# display_board_ATMega4809.net
KiCad netlist of a schematic drawn in EAGLE
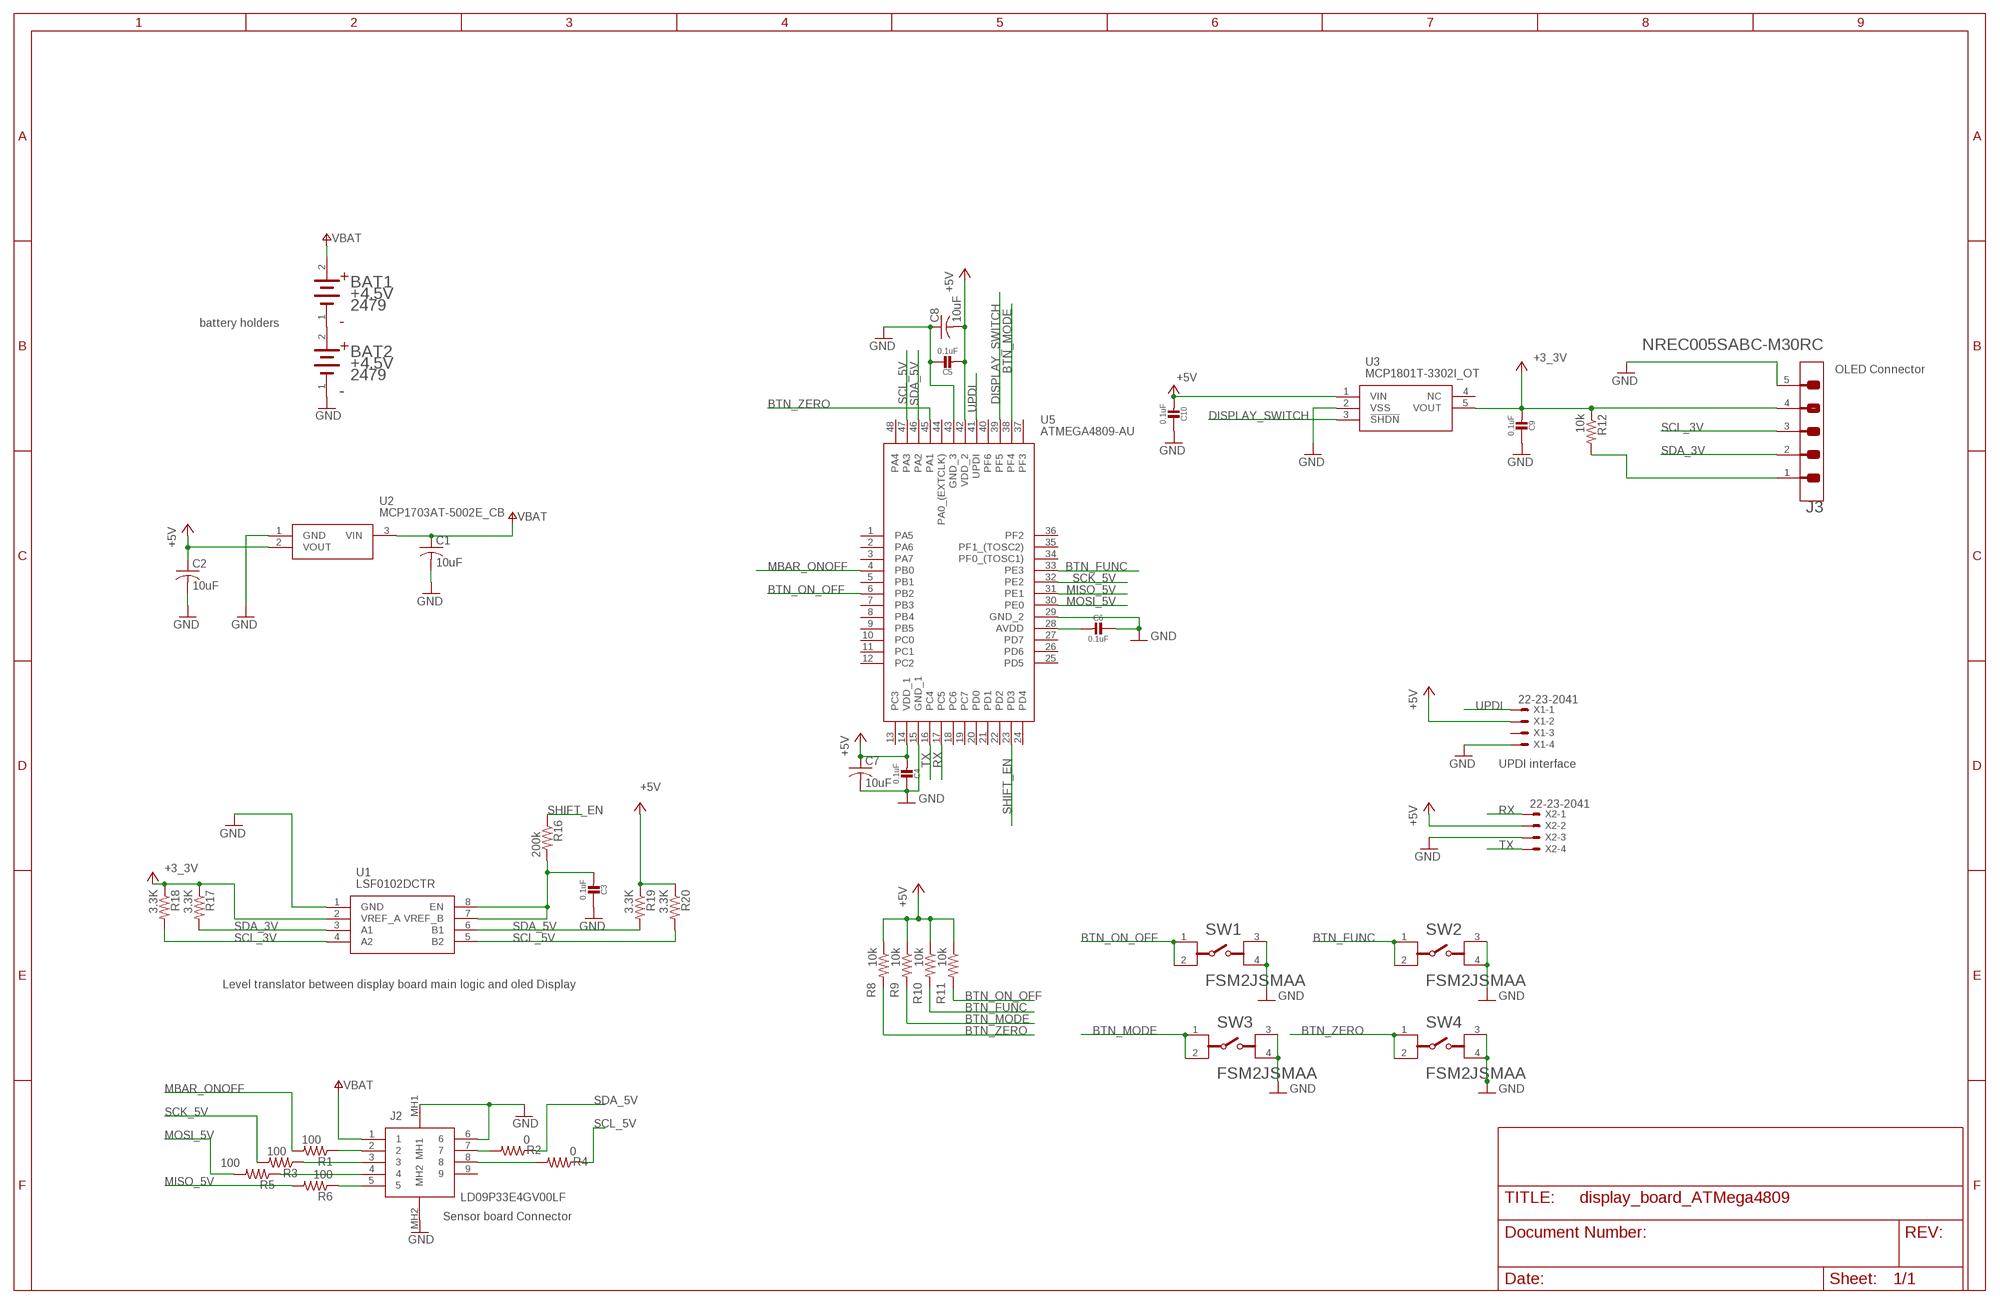
[diagram p0: schematic, sheet 1]

(export (version "E")
  (design (tool "Eeschema 10.0.6"))
  (components
    (comp (ref "BAT1")
      (value "KEYSTONE_2479KEYSTONE_2479_0_0")
      (footprint "eagle-import:KEYSTONE_2479_0")
      (fields
        (field (name "DIGIKEY_PART_NUMBER") "36-2479-ND")
        (field (name "MF") "Keystone")
        (field (name "MOUSER_PART_NUMBER") "534-2479")
      )
      (libsource (lib "eagle-import") (part "KEYSTONE_2479KEYSTONE_2479_0_0"))
    )
    (comp (ref "BAT2")
      (value "KEYSTONE_2479KEYSTONE_2479_0_0")
      (footprint "eagle-import:KEYSTONE_2479_0")
      (fields
        (field (name "DIGIKEY_PART_NUMBER") "36-2479-ND")
        (field (name "MF") "Keystone")
        (field (name "MOUSER_PART_NUMBER") "534-2479")
      )
      (libsource (lib "eagle-import") (part "KEYSTONE_2479KEYSTONE_2479_0_0"))
    )
    (comp (ref "C1")
      (value "10uF")
      (footprint "eagle-import:C0805")
      (libsource (lib "eagle-import") (part "C-USC0805"))
    )
    (comp (ref "C2")
      (value "10uF")
      (footprint "eagle-import:C0805")
      (libsource (lib "eagle-import") (part "C-USC0805"))
    )
    (comp (ref "C3")
      (value "0.1uF")
      (footprint "eagle-import:_0603MP")
      (libsource (lib "eagle-import") (part "CAP_CERAMIC_0603MP"))
    )
    (comp (ref "C4")
      (value "0.1uF")
      (footprint "eagle-import:_0603MP")
      (libsource (lib "eagle-import") (part "CAP_CERAMIC_0603MP"))
    )
    (comp (ref "C5")
      (value "0.1uF")
      (footprint "eagle-import:_0603MP")
      (libsource (lib "eagle-import") (part "CAP_CERAMIC_0603MP"))
    )
    (comp (ref "C6")
      (value "0.1uF")
      (footprint "eagle-import:_0603MP")
      (libsource (lib "eagle-import") (part "CAP_CERAMIC_0603MP"))
    )
    (comp (ref "C7")
      (value "10uF")
      (footprint "eagle-import:C0805")
      (libsource (lib "eagle-import") (part "C-USC0805"))
    )
    (comp (ref "C8")
      (value "10uF")
      (footprint "eagle-import:C0805")
      (libsource (lib "eagle-import") (part "C-USC0805"))
    )
    (comp (ref "C9")
      (value "0.1uF")
      (footprint "eagle-import:_0603MP")
      (libsource (lib "eagle-import") (part "CAP_CERAMIC_0603MP"))
    )
    (comp (ref "C10")
      (value "0.1uF")
      (footprint "eagle-import:_0603MP")
      (libsource (lib "eagle-import") (part "CAP_CERAMIC_0603MP"))
    )
    (comp (ref "J2")
      (value "LD09P33E4GV00LF")
      (footprint "eagle-import:LD09P33E4GV00LF")
      (fields (field (name "MOUSER_PART_NUMBER") "649-LD09P33E4GV00LF"))
      (libsource (lib "eagle-import") (part "LD09P33E4GV00LF"))
    )
    (comp (ref "J3")
      (value "SULLINS_NREC005SABC-M30RCSULLINS_NREC005SABC-M30RC_0_0")
      (footprint "eagle-import:SULLINS_NREC005SABC-M30RC_0")
      (fields
        (field (name "DIGIKEY_PART_NUMBER") "CONN HEADER .100\" SNGL SMD 5POS")
        (field (name "MF") "Sullins")
        (field (name "MPN") "NREC005SABC-M30RC")
      )
      (libsource (lib "eagle-import") (part "SULLINS_NREC005SABC-M30RCSULLINS_NREC005SABC-M30RC_0_0"))
    )
    (comp (ref "R1")
      (value "100")
      (footprint "eagle-import:R0603")
      (libsource (lib "eagle-import") (part "R-US_R0603"))
    )
    (comp (ref "R2")
      (value "0")
      (footprint "eagle-import:R0603")
      (libsource (lib "eagle-import") (part "R-US_R0603"))
    )
    (comp (ref "R3")
      (value "100")
      (footprint "eagle-import:R0603")
      (libsource (lib "eagle-import") (part "R-US_R0603"))
    )
    (comp (ref "R4")
      (value "0")
      (footprint "eagle-import:R0603")
      (libsource (lib "eagle-import") (part "R-US_R0603"))
    )
    (comp (ref "R5")
      (value "100")
      (footprint "eagle-import:R0603")
      (libsource (lib "eagle-import") (part "R-US_R0603"))
    )
    (comp (ref "R6")
      (value "100")
      (footprint "eagle-import:R0603")
      (libsource (lib "eagle-import") (part "R-US_R0603"))
    )
    (comp (ref "R8")
      (value "10k")
      (footprint "eagle-import:R0603")
      (libsource (lib "eagle-import") (part "R-US_R0603"))
    )
    (comp (ref "R9")
      (value "10k")
      (footprint "eagle-import:R0603")
      (libsource (lib "eagle-import") (part "R-US_R0603"))
    )
    (comp (ref "R10")
      (value "10k")
      (footprint "eagle-import:R0603")
      (libsource (lib "eagle-import") (part "R-US_R0603"))
    )
    (comp (ref "R11")
      (value "10k")
      (footprint "eagle-import:R0603")
      (libsource (lib "eagle-import") (part "R-US_R0603"))
    )
    (comp (ref "R12")
      (value "10k")
      (footprint "eagle-import:R0603")
      (libsource (lib "eagle-import") (part "R-US_R0603"))
    )
    (comp (ref "R16")
      (value "200k")
      (footprint "eagle-import:R0603")
      (libsource (lib "eagle-import") (part "R-US_R0603"))
    )
    (comp (ref "R17")
      (value "3.3K")
      (footprint "eagle-import:R0603")
      (libsource (lib "eagle-import") (part "R-US_R0603"))
    )
    (comp (ref "R18")
      (value "3.3K")
      (footprint "eagle-import:R0603")
      (libsource (lib "eagle-import") (part "R-US_R0603"))
    )
    (comp (ref "R19")
      (value "3.3K")
      (footprint "eagle-import:R0603")
      (libsource (lib "eagle-import") (part "R-US_R0603"))
    )
    (comp (ref "R20")
      (value "3.3K")
      (footprint "eagle-import:R0603")
      (libsource (lib "eagle-import") (part "R-US_R0603"))
    )
    (comp (ref "SW1")
      (value "TE_CONNECTIVITY_FSM2JSMAATE_CONNECTIVITY_FSM2JSMAA_0_0")
      (footprint "eagle-import:TE_CONNECTIVITY_FSM2JSMAA_0")
      (fields
        (field (name "DIGIKEY_PART_NUMBER") "450-3355-ND")
        (field (name "MF") "TE Connectivity")
        (field (name "MOUSER_PART_NUMBER") "506-2-1437565-8")
      )
      (libsource (lib "eagle-import") (part "TE_CONNECTIVITY_FSM2JSMAATE_CONNECTIVITY_FSM2JSMAA_0_0"))
    )
    (comp (ref "SW2")
      (value "TE_CONNECTIVITY_FSM2JSMAATE_CONNECTIVITY_FSM2JSMAA_0_0")
      (footprint "eagle-import:TE_CONNECTIVITY_FSM2JSMAA_0")
      (fields
        (field (name "DIGIKEY_PART_NUMBER") "450-3355-ND")
        (field (name "MF") "TE Connectivity")
        (field (name "MOUSER_PART_NUMBER") "506-2-1437565-8")
      )
      (libsource (lib "eagle-import") (part "TE_CONNECTIVITY_FSM2JSMAATE_CONNECTIVITY_FSM2JSMAA_0_0"))
    )
    (comp (ref "SW3")
      (value "TE_CONNECTIVITY_FSM2JSMAATE_CONNECTIVITY_FSM2JSMAA_0_0")
      (footprint "eagle-import:TE_CONNECTIVITY_FSM2JSMAA_0")
      (fields
        (field (name "DIGIKEY_PART_NUMBER") "450-3355-ND")
        (field (name "MF") "TE Connectivity")
        (field (name "MOUSER_PART_NUMBER") "506-2-1437565-8")
      )
      (libsource (lib "eagle-import") (part "TE_CONNECTIVITY_FSM2JSMAATE_CONNECTIVITY_FSM2JSMAA_0_0"))
    )
    (comp (ref "SW4")
      (value "TE_CONNECTIVITY_FSM2JSMAATE_CONNECTIVITY_FSM2JSMAA_0_0")
      (footprint "eagle-import:TE_CONNECTIVITY_FSM2JSMAA_0")
      (fields
        (field (name "DIGIKEY_PART_NUMBER") "450-3355-ND")
        (field (name "MF") "TE Connectivity")
        (field (name "MOUSER_PART_NUMBER") "506-2-1437565-8")
      )
      (libsource (lib "eagle-import") (part "TE_CONNECTIVITY_FSM2JSMAATE_CONNECTIVITY_FSM2JSMAA_0_0"))
    )
    (comp (ref "U1")
      (value "LSF0102DCTR")
      (footprint "eagle-import:SOP65P400X130-8N")
      (fields (field (name "MOUSER_PART_NUMBER") "595-LSF0102DCTR"))
      (libsource (lib "eagle-import") (part "LSF0102DCTR"))
    )
    (comp (ref "U2")
      (value "MCP1703AT-5002E_CB")
      (footprint "eagle-import:SOT95P255X145-3N")
      (fields
        (field (name "ARROW_PART_NUMBER") "MCP1703AT-5002E/CB")
        (field (name "MOUSER_PART_NUMBER") "579-MCP1703AT5002ECB")
      )
      (libsource (lib "eagle-import") (part "MCP1703AT-5002E_CB"))
    )
    (comp (ref "U3")
      (value "MCP1801T-3302I_OT")
      (footprint "eagle-import:SOT95P270X145-5N")
      (fields
        (field (name "ARROW_PART_NUMBER") "MCP1801T-3302I/OT")
        (field (name "MOUSER_PART_NUMBER") "579-MCP1801T-3302IOT")
      )
      (libsource (lib "eagle-import") (part "MCP1801T-3302I_OT"))
    )
    (comp (ref "U5")
      (value "ATMEGA4809-AU")
      (footprint "eagle-import:QFP50P900X900X120-48N")
      (fields (field (name "MOUSER_PART_NUMBER") "556-ATMEGA4809-AU"))
      (libsource (lib "eagle-import") (part "ATMEGA4809-AU"))
    )
    (comp (ref "X1")
      (value "22-23-2041")
      (footprint "eagle-import:22-23-2041")
      (fields (field (name "MF") "MOLEX"))
      (libsource (lib "eagle-import") (part "22-23-2041"))
    )
    (comp (ref "X2")
      (value "22-23-2041")
      (footprint "eagle-import:22-23-2041")
      (fields (field (name "MF") "MOLEX"))
      (libsource (lib "eagle-import") (part "22-23-2041"))
    )
  )
  (nets
    (net (code "1") (name "+3_3V") (class "Default")
      (node (ref "C9") (pin "2") (pinfunction "2_2") (pintype "passive"))
      (node (ref "J3") (pin "4") (pinfunction "4_4") (pintype "bidirectional"))
      (node (ref "R12") (pin "1") (pinfunction "1_1") (pintype "passive"))
      (node (ref "R17") (pin "1") (pinfunction "1_1") (pintype "passive"))
      (node (ref "R18") (pin "1") (pinfunction "1_1") (pintype "passive"))
      (node (ref "U1") (pin "2") (pinfunction "VREF_A_2") (pintype "bidirectional"))
      (node (ref "U3") (pin "5") (pinfunction "VOUT_5") (pintype "output"))
    )
    (net (code "2") (name "+5V") (class "Default")
      (node (ref "C10") (pin "2") (pinfunction "2_2") (pintype "passive"))
      (node (ref "C2") (pin "1") (pinfunction "1_1") (pintype "passive"))
      (node (ref "C4") (pin "2") (pinfunction "2_2") (pintype "passive"))
      (node (ref "C5") (pin "2") (pinfunction "2_2") (pintype "passive"))
      (node (ref "C7") (pin "1") (pinfunction "1_1") (pintype "passive"))
      (node (ref "C8") (pin "2") (pinfunction "2_2") (pintype "passive"))
      (node (ref "R10") (pin "1") (pinfunction "1_1") (pintype "passive"))
      (node (ref "R11") (pin "1") (pinfunction "1_1") (pintype "passive"))
      (node (ref "R19") (pin "1") (pinfunction "1_1") (pintype "passive"))
      (node (ref "R20") (pin "1") (pinfunction "1_1") (pintype "passive"))
      (node (ref "R8") (pin "1") (pinfunction "1_1") (pintype "passive"))
      (node (ref "R9") (pin "1") (pinfunction "1_1") (pintype "passive"))
      (node (ref "U2") (pin "2") (pinfunction "VOUT_2") (pintype "bidirectional"))
      (node (ref "U3") (pin "1") (pinfunction "VIN_1") (pintype "input"))
      (node (ref "U5") (pin "14") (pinfunction "VDD_1_14") (pintype "bidirectional"))
      (node (ref "U5") (pin "42") (pinfunction "VDD_2_42") (pintype "bidirectional"))
      (node (ref "X1") (pin "2") (pinfunction "S_2") (pintype "passive"))
      (node (ref "X2") (pin "2") (pinfunction "S_2") (pintype "passive"))
    )
    (net (code "3") (name "/BTN_FUNC") (class "Default")
      (node (ref "R10") (pin "2") (pinfunction "2_2") (pintype "passive"))
      (node (ref "SW2") (pin "1") (pinfunction "1_1") (pintype "passive"))
      (node (ref "SW2") (pin "2") (pinfunction "2_2") (pintype "passive"))
      (node (ref "U5") (pin "33") (pinfunction "PE3_33") (pintype "bidirectional"))
    )
    (net (code "4") (name "/BTN_MODE") (class "Default")
      (node (ref "R9") (pin "2") (pinfunction "2_2") (pintype "passive"))
      (node (ref "SW3") (pin "1") (pinfunction "1_1") (pintype "passive"))
      (node (ref "SW3") (pin "2") (pinfunction "2_2") (pintype "passive"))
      (node (ref "U5") (pin "38") (pinfunction "PF4_38") (pintype "bidirectional"))
    )
    (net (code "5") (name "/BTN_ON_OFF") (class "Default")
      (node (ref "R11") (pin "2") (pinfunction "2_2") (pintype "passive"))
      (node (ref "SW1") (pin "1") (pinfunction "1_1") (pintype "passive"))
      (node (ref "SW1") (pin "2") (pinfunction "2_2") (pintype "passive"))
      (node (ref "U5") (pin "6") (pinfunction "PB2_6") (pintype "bidirectional"))
    )
    (net (code "6") (name "/BTN_ZERO") (class "Default")
      (node (ref "R8") (pin "2") (pinfunction "2_2") (pintype "passive"))
      (node (ref "SW4") (pin "1") (pinfunction "1_1") (pintype "passive"))
      (node (ref "SW4") (pin "2") (pinfunction "2_2") (pintype "passive"))
      (node (ref "U5") (pin "45") (pinfunction "PA1_45") (pintype "bidirectional"))
    )
    (net (code "7") (name "/DISPLAY_SWITCH") (class "Default")
      (node (ref "U3") (pin "3") (pinfunction "~{SHDN}_3") (pintype "bidirectional"))
      (node (ref "U5") (pin "39") (pinfunction "PF5_39") (pintype "bidirectional"))
    )
    (net (code "8") (name "/MBAR_ONOFF") (class "Default")
      (node (ref "R1") (pin "2") (pinfunction "2_2") (pintype "passive"))
      (node (ref "U5") (pin "4") (pinfunction "PB0_4") (pintype "bidirectional"))
    )
    (net (code "9") (name "/MISO_5V") (class "Default")
      (node (ref "R6") (pin "2") (pinfunction "2_2") (pintype "passive"))
      (node (ref "U5") (pin "31") (pinfunction "PE1_31") (pintype "bidirectional"))
    )
    (net (code "10") (name "/MOSI_5V") (class "Default")
      (node (ref "R5") (pin "2") (pinfunction "2_2") (pintype "passive"))
      (node (ref "U5") (pin "30") (pinfunction "PE0_30") (pintype "bidirectional"))
    )
    (net (code "11") (name "/RX") (class "Default")
      (node (ref "U5") (pin "17") (pinfunction "PC5_17") (pintype "bidirectional"))
      (node (ref "X2") (pin "1") (pinfunction "S_1") (pintype "passive"))
    )
    (net (code "12") (name "/SCK_5V") (class "Default")
      (node (ref "R3") (pin "2") (pinfunction "2_2") (pintype "passive"))
      (node (ref "U5") (pin "32") (pinfunction "PE2_32") (pintype "bidirectional"))
    )
    (net (code "13") (name "/SCL_3V") (class "Default")
      (node (ref "J3") (pin "3") (pinfunction "3_3") (pintype "bidirectional"))
      (node (ref "R18") (pin "2") (pinfunction "2_2") (pintype "passive"))
      (node (ref "U1") (pin "4") (pinfunction "A2_4") (pintype "bidirectional"))
    )
    (net (code "14") (name "/SCL_5V") (class "Default")
      (node (ref "R20") (pin "2") (pinfunction "2_2") (pintype "passive"))
      (node (ref "R4") (pin "1") (pinfunction "1_1") (pintype "passive"))
      (node (ref "U1") (pin "5") (pinfunction "B2_5") (pintype "bidirectional"))
      (node (ref "U5") (pin "47") (pinfunction "PA3_47") (pintype "bidirectional"))
    )
    (net (code "15") (name "/SDA_3V") (class "Default")
      (node (ref "J3") (pin "2") (pinfunction "2_2") (pintype "bidirectional"))
      (node (ref "R17") (pin "2") (pinfunction "2_2") (pintype "passive"))
      (node (ref "U1") (pin "3") (pinfunction "A1_3") (pintype "bidirectional"))
    )
    (net (code "16") (name "/SDA_5V") (class "Default")
      (node (ref "R19") (pin "2") (pinfunction "2_2") (pintype "passive"))
      (node (ref "R2") (pin "1") (pinfunction "1_1") (pintype "passive"))
      (node (ref "U1") (pin "6") (pinfunction "B1_6") (pintype "bidirectional"))
      (node (ref "U5") (pin "46") (pinfunction "PA2_46") (pintype "bidirectional"))
    )
    (net (code "17") (name "/SHIFT_EN") (class "Default")
      (node (ref "R16") (pin "1") (pinfunction "1_1") (pintype "passive"))
      (node (ref "U5") (pin "23") (pinfunction "PD3_23") (pintype "bidirectional"))
    )
    (net (code "18") (name "/TX") (class "Default")
      (node (ref "U5") (pin "16") (pinfunction "PC4_16") (pintype "bidirectional"))
      (node (ref "X2") (pin "4") (pinfunction "S_4") (pintype "passive"))
    )
    (net (code "19") (name "/UPDI") (class "Default")
      (node (ref "U5") (pin "41") (pinfunction "UPDI_41") (pintype "bidirectional"))
      (node (ref "X1") (pin "1") (pinfunction "S_1") (pintype "passive"))
    )
    (net (code "20") (name "GND") (class "Default")
      (node (ref "BAT2") (pin "1") (pinfunction "CATHODE_1") (pintype "bidirectional"))
      (node (ref "C1") (pin "2") (pinfunction "2_2") (pintype "passive"))
      (node (ref "C10") (pin "1") (pinfunction "1_1") (pintype "passive"))
      (node (ref "C2") (pin "2") (pinfunction "2_2") (pintype "passive"))
      (node (ref "C3") (pin "1") (pinfunction "1_1") (pintype "passive"))
      (node (ref "C4") (pin "1") (pinfunction "1_1") (pintype "passive"))
      (node (ref "C5") (pin "1") (pinfunction "1_1") (pintype "passive"))
      (node (ref "C6") (pin "1") (pinfunction "1_1") (pintype "passive"))
      (node (ref "C7") (pin "2") (pinfunction "2_2") (pintype "passive"))
      (node (ref "C8") (pin "1") (pinfunction "1_1") (pintype "passive"))
      (node (ref "C9") (pin "1") (pinfunction "1_1") (pintype "passive"))
      (node (ref "J2") (pin "6") (pinfunction "6_6") (pintype "bidirectional"))
      (node (ref "J2") (pin "MH1") (pinfunction "MH1_MH1") (pintype "bidirectional"))
      (node (ref "J2") (pin "MH2") (pinfunction "MH2_MH2") (pintype "bidirectional"))
      (node (ref "J3") (pin "5") (pinfunction "5_5") (pintype "bidirectional"))
      (node (ref "SW1") (pin "3") (pinfunction "3_3") (pintype "passive"))
      (node (ref "SW1") (pin "4") (pinfunction "4_4") (pintype "passive"))
      (node (ref "SW2") (pin "3") (pinfunction "3_3") (pintype "passive"))
      (node (ref "SW2") (pin "4") (pinfunction "4_4") (pintype "passive"))
      (node (ref "SW3") (pin "3") (pinfunction "3_3") (pintype "passive"))
      (node (ref "SW3") (pin "4") (pinfunction "4_4") (pintype "passive"))
      (node (ref "SW4") (pin "3") (pinfunction "3_3") (pintype "passive"))
      (node (ref "SW4") (pin "4") (pinfunction "4_4") (pintype "passive"))
      (node (ref "U1") (pin "1") (pinfunction "GND_1") (pintype "bidirectional"))
      (node (ref "U2") (pin "1") (pinfunction "GND_1") (pintype "bidirectional"))
      (node (ref "U3") (pin "2") (pinfunction "VSS_2") (pintype "power_in"))
      (node (ref "U5") (pin "15") (pinfunction "GND_1_15") (pintype "bidirectional"))
      (node (ref "U5") (pin "29") (pinfunction "GND_2_29") (pintype "bidirectional"))
      (node (ref "U5") (pin "43") (pinfunction "GND_3_43") (pintype "bidirectional"))
      (node (ref "X1") (pin "4") (pinfunction "S_4") (pintype "passive"))
      (node (ref "X2") (pin "3") (pinfunction "S_3") (pintype "passive"))
    )
    (net (code "21") (name "Net-(BAT1-CATHODE)") (class "Default")
      (node (ref "BAT1") (pin "1") (pinfunction "CATHODE_1") (pintype "bidirectional"))
      (node (ref "BAT2") (pin "2") (pinfunction "ANODE_2") (pintype "bidirectional"))
    )
    (net (code "22") (name "Net-(J2-Pad2)") (class "Default")
      (node (ref "J2") (pin "2") (pinfunction "2_2") (pintype "bidirectional"))
      (node (ref "R1") (pin "1") (pinfunction "1_1") (pintype "passive"))
    )
    (net (code "23") (name "Net-(J2-Pad3)") (class "Default")
      (node (ref "J2") (pin "3") (pinfunction "3_3") (pintype "bidirectional"))
      (node (ref "R3") (pin "1") (pinfunction "1_1") (pintype "passive"))
    )
    (net (code "24") (name "Net-(J2-Pad4)") (class "Default")
      (node (ref "J2") (pin "4") (pinfunction "4_4") (pintype "bidirectional"))
      (node (ref "R5") (pin "1") (pinfunction "1_1") (pintype "passive"))
    )
    (net (code "25") (name "Net-(J2-Pad5)") (class "Default")
      (node (ref "J2") (pin "5") (pinfunction "5_5") (pintype "bidirectional"))
      (node (ref "R6") (pin "1") (pinfunction "1_1") (pintype "passive"))
    )
    (net (code "26") (name "Net-(J2-Pad7)") (class "Default")
      (node (ref "J2") (pin "7") (pinfunction "7_7") (pintype "bidirectional"))
      (node (ref "R2") (pin "2") (pinfunction "2_2") (pintype "passive"))
    )
    (net (code "27") (name "Net-(J2-Pad8)") (class "Default")
      (node (ref "J2") (pin "8") (pinfunction "8_8") (pintype "bidirectional"))
      (node (ref "R4") (pin "2") (pinfunction "2_2") (pintype "passive"))
    )
    (net (code "28") (name "Net-(J3-Pad1)") (class "Default")
      (node (ref "J3") (pin "1") (pinfunction "1_1") (pintype "bidirectional"))
      (node (ref "R12") (pin "2") (pinfunction "2_2") (pintype "passive"))
    )
    (net (code "29") (name "Net-(U1-EN)") (class "Default")
      (node (ref "C3") (pin "2") (pinfunction "2_2") (pintype "passive"))
      (node (ref "R16") (pin "2") (pinfunction "2_2") (pintype "passive"))
      (node (ref "U1") (pin "7") (pinfunction "VREF_B_7") (pintype "bidirectional"))
      (node (ref "U1") (pin "8") (pinfunction "EN_8") (pintype "bidirectional"))
    )
    (net (code "30") (name "Net-(U5-AVDD)") (class "Default")
      (node (ref "C6") (pin "2") (pinfunction "2_2") (pintype "passive"))
      (node (ref "U5") (pin "28") (pinfunction "AVDD_28") (pintype "bidirectional"))
    )
    (net (code "31") (name "VBAT") (class "Default")
      (node (ref "BAT1") (pin "2") (pinfunction "ANODE_2") (pintype "bidirectional"))
      (node (ref "C1") (pin "1") (pinfunction "1_1") (pintype "passive"))
      (node (ref "J2") (pin "1") (pinfunction "1_1") (pintype "bidirectional"))
      (node (ref "U2") (pin "3") (pinfunction "VIN_3") (pintype "bidirectional"))
    )
    (net (code "32") (name "unconnected-(J2-Pad9)") (class "Default")
      (node (ref "J2") (pin "9") (pinfunction "9_9") (pintype "bidirectional"))
    )
    (net (code "33") (name "unconnected-(U3-NC-Pad4)") (class "Default")
      (node (ref "U3") (pin "4") (pinfunction "NC_4") (pintype "no_connect"))
    )
    (net (code "34") (name "unconnected-(U5-PA0_(EXTCLK)-Pad44)") (class "Default")
      (node (ref "U5") (pin "44") (pinfunction "PA0_(EXTCLK)_44") (pintype "bidirectional"))
    )
    (net (code "35") (name "unconnected-(U5-PA4-Pad48)") (class "Default")
      (node (ref "U5") (pin "48") (pinfunction "PA4_48") (pintype "bidirectional"))
    )
    (net (code "36") (name "unconnected-(U5-PA5-Pad1)") (class "Default")
      (node (ref "U5") (pin "1") (pinfunction "PA5_1") (pintype "bidirectional"))
    )
    (net (code "37") (name "unconnected-(U5-PA6-Pad2)") (class "Default")
      (node (ref "U5") (pin "2") (pinfunction "PA6_2") (pintype "bidirectional"))
    )
    (net (code "38") (name "unconnected-(U5-PA7-Pad3)") (class "Default")
      (node (ref "U5") (pin "3") (pinfunction "PA7_3") (pintype "bidirectional"))
    )
    (net (code "39") (name "unconnected-(U5-PB1-Pad5)") (class "Default")
      (node (ref "U5") (pin "5") (pinfunction "PB1_5") (pintype "bidirectional"))
    )
    (net (code "40") (name "unconnected-(U5-PB3-Pad7)") (class "Default")
      (node (ref "U5") (pin "7") (pinfunction "PB3_7") (pintype "bidirectional"))
    )
    (net (code "41") (name "unconnected-(U5-PB4-Pad8)") (class "Default")
      (node (ref "U5") (pin "8") (pinfunction "PB4_8") (pintype "bidirectional"))
    )
    (net (code "42") (name "unconnected-(U5-PB5-Pad9)") (class "Default")
      (node (ref "U5") (pin "9") (pinfunction "PB5_9") (pintype "bidirectional"))
    )
    (net (code "43") (name "unconnected-(U5-PC0-Pad10)") (class "Default")
      (node (ref "U5") (pin "10") (pinfunction "PC0_10") (pintype "bidirectional"))
    )
    (net (code "44") (name "unconnected-(U5-PC1-Pad11)") (class "Default")
      (node (ref "U5") (pin "11") (pinfunction "PC1_11") (pintype "bidirectional"))
    )
    (net (code "45") (name "unconnected-(U5-PC2-Pad12)") (class "Default")
      (node (ref "U5") (pin "12") (pinfunction "PC2_12") (pintype "bidirectional"))
    )
    (net (code "46") (name "unconnected-(U5-PC3-Pad13)") (class "Default")
      (node (ref "U5") (pin "13") (pinfunction "PC3_13") (pintype "bidirectional"))
    )
    (net (code "47") (name "unconnected-(U5-PC6-Pad18)") (class "Default")
      (node (ref "U5") (pin "18") (pinfunction "PC6_18") (pintype "bidirectional"))
    )
    (net (code "48") (name "unconnected-(U5-PC7-Pad19)") (class "Default")
      (node (ref "U5") (pin "19") (pinfunction "PC7_19") (pintype "bidirectional"))
    )
    (net (code "49") (name "unconnected-(U5-PD0-Pad20)") (class "Default")
      (node (ref "U5") (pin "20") (pinfunction "PD0_20") (pintype "bidirectional"))
    )
    (net (code "50") (name "unconnected-(U5-PD1-Pad21)") (class "Default")
      (node (ref "U5") (pin "21") (pinfunction "PD1_21") (pintype "bidirectional"))
    )
    (net (code "51") (name "unconnected-(U5-PD2-Pad22)") (class "Default")
      (node (ref "U5") (pin "22") (pinfunction "PD2_22") (pintype "bidirectional"))
    )
    (net (code "52") (name "unconnected-(U5-PD4-Pad24)") (class "Default")
      (node (ref "U5") (pin "24") (pinfunction "PD4_24") (pintype "bidirectional"))
    )
    (net (code "53") (name "unconnected-(U5-PD5-Pad25)") (class "Default")
      (node (ref "U5") (pin "25") (pinfunction "PD5_25") (pintype "bidirectional"))
    )
    (net (code "54") (name "unconnected-(U5-PD6-Pad26)") (class "Default")
      (node (ref "U5") (pin "26") (pinfunction "PD6_26") (pintype "bidirectional"))
    )
    (net (code "55") (name "unconnected-(U5-PD7-Pad27)") (class "Default")
      (node (ref "U5") (pin "27") (pinfunction "PD7_27") (pintype "bidirectional"))
    )
    (net (code "56") (name "unconnected-(U5-PF0_(TOSC1)-Pad34)") (class "Default")
      (node (ref "U5") (pin "34") (pinfunction "PF0_(TOSC1)_34") (pintype "bidirectional"))
    )
    (net (code "57") (name "unconnected-(U5-PF1_(TOSC2)-Pad35)") (class "Default")
      (node (ref "U5") (pin "35") (pinfunction "PF1_(TOSC2)_35") (pintype "bidirectional"))
    )
    (net (code "58") (name "unconnected-(U5-PF2-Pad36)") (class "Default")
      (node (ref "U5") (pin "36") (pinfunction "PF2_36") (pintype "bidirectional"))
    )
    (net (code "59") (name "unconnected-(U5-PF3-Pad37)") (class "Default")
      (node (ref "U5") (pin "37") (pinfunction "PF3_37") (pintype "bidirectional"))
    )
    (net (code "60") (name "unconnected-(U5-PF6-Pad40)") (class "Default")
      (node (ref "U5") (pin "40") (pinfunction "PF6_40") (pintype "bidirectional"))
    )
    (net (code "61") (name "unconnected-(X1C-S-Pad3)") (class "Default")
      (node (ref "X1") (pin "3") (pinfunction "S_3") (pintype "passive"))
    )
  )
)
